# LogicLab1G.net
KiCad netlist of a schematic drawn in EAGLE
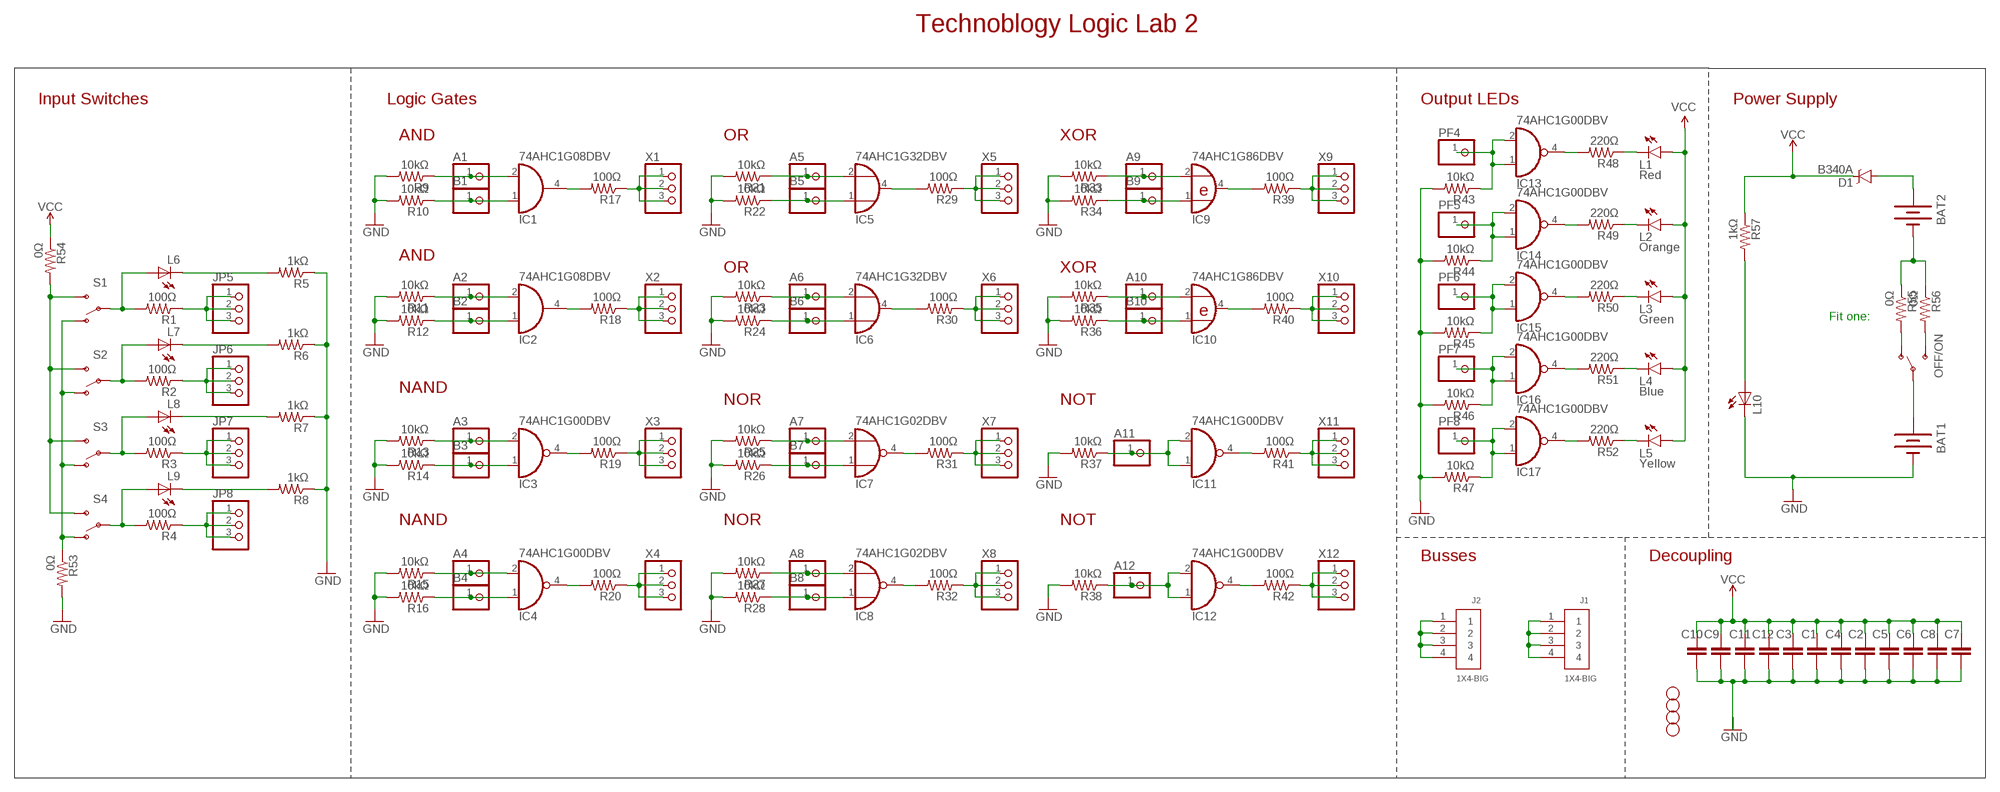
[diagram p0: schematic, sheet 1]

(export (version "E")
  (design (tool "Eeschema 10.0.6"))
  (components
    (comp (ref "A1")
      (value "PINHD-1X1")
      (footprint "eagle-import:1X01")
      (libsource (lib "eagle-import") (part "PINHD-1X1"))
    )
    (comp (ref "A2")
      (value "PINHD-1X1")
      (footprint "eagle-import:1X01")
      (libsource (lib "eagle-import") (part "PINHD-1X1"))
    )
    (comp (ref "A3")
      (value "PINHD-1X1")
      (footprint "eagle-import:1X01")
      (libsource (lib "eagle-import") (part "PINHD-1X1"))
    )
    (comp (ref "A4")
      (value "PINHD-1X1")
      (footprint "eagle-import:1X01")
      (libsource (lib "eagle-import") (part "PINHD-1X1"))
    )
    (comp (ref "A5")
      (value "PINHD-1X1")
      (footprint "eagle-import:1X01")
      (libsource (lib "eagle-import") (part "PINHD-1X1"))
    )
    (comp (ref "A6")
      (value "PINHD-1X1")
      (footprint "eagle-import:1X01")
      (libsource (lib "eagle-import") (part "PINHD-1X1"))
    )
    (comp (ref "A7")
      (value "PINHD-1X1")
      (footprint "eagle-import:1X01")
      (libsource (lib "eagle-import") (part "PINHD-1X1"))
    )
    (comp (ref "A8")
      (value "PINHD-1X1")
      (footprint "eagle-import:1X01")
      (libsource (lib "eagle-import") (part "PINHD-1X1"))
    )
    (comp (ref "A9")
      (value "PINHD-1X1")
      (footprint "eagle-import:1X01")
      (libsource (lib "eagle-import") (part "PINHD-1X1"))
    )
    (comp (ref "A10")
      (value "PINHD-1X1")
      (footprint "eagle-import:1X01")
      (libsource (lib "eagle-import") (part "PINHD-1X1"))
    )
    (comp (ref "A11")
      (value "PINHD-1X1")
      (footprint "eagle-import:1X01")
      (libsource (lib "eagle-import") (part "PINHD-1X1"))
    )
    (comp (ref "A12")
      (value "PINHD-1X1")
      (footprint "eagle-import:1X01")
      (libsource (lib "eagle-import") (part "PINHD-1X1"))
    )
    (comp (ref "B1")
      (value "PINHD-1X1")
      (footprint "eagle-import:1X01")
      (libsource (lib "eagle-import") (part "PINHD-1X1"))
    )
    (comp (ref "B2")
      (value "PINHD-1X1")
      (footprint "eagle-import:1X01")
      (libsource (lib "eagle-import") (part "PINHD-1X1"))
    )
    (comp (ref "B3")
      (value "PINHD-1X1")
      (footprint "eagle-import:1X01")
      (libsource (lib "eagle-import") (part "PINHD-1X1"))
    )
    (comp (ref "B4")
      (value "PINHD-1X1")
      (footprint "eagle-import:1X01")
      (libsource (lib "eagle-import") (part "PINHD-1X1"))
    )
    (comp (ref "B5")
      (value "PINHD-1X1")
      (footprint "eagle-import:1X01")
      (libsource (lib "eagle-import") (part "PINHD-1X1"))
    )
    (comp (ref "B6")
      (value "PINHD-1X1")
      (footprint "eagle-import:1X01")
      (libsource (lib "eagle-import") (part "PINHD-1X1"))
    )
    (comp (ref "B7")
      (value "PINHD-1X1")
      (footprint "eagle-import:1X01")
      (libsource (lib "eagle-import") (part "PINHD-1X1"))
    )
    (comp (ref "B8")
      (value "PINHD-1X1")
      (footprint "eagle-import:1X01")
      (libsource (lib "eagle-import") (part "PINHD-1X1"))
    )
    (comp (ref "B9")
      (value "PINHD-1X1")
      (footprint "eagle-import:1X01")
      (libsource (lib "eagle-import") (part "PINHD-1X1"))
    )
    (comp (ref "B10")
      (value "PINHD-1X1")
      (footprint "eagle-import:1X01")
      (libsource (lib "eagle-import") (part "PINHD-1X1"))
    )
    (comp (ref "BAT1")
      (value "BATTERYAAA-KIT")
      (footprint "eagle-import:BATTERY-AAA-KIT")
      (libsource (lib "eagle-import") (part "BATTERYAAA-KIT"))
    )
    (comp (ref "BAT2")
      (value "BATTERYAAA-KIT")
      (footprint "eagle-import:BATTERY-AAA-KIT")
      (libsource (lib "eagle-import") (part "BATTERYAAA-KIT"))
    )
    (comp (ref "C1")
      (value "100n")
      (footprint "eagle-import:0805")
      (libsource (lib "eagle-import") (part "CAP0805"))
    )
    (comp (ref "C2")
      (value "100n")
      (footprint "eagle-import:0805")
      (libsource (lib "eagle-import") (part "CAP0805"))
    )
    (comp (ref "C3")
      (value "100n")
      (footprint "eagle-import:0805")
      (libsource (lib "eagle-import") (part "CAP0805"))
    )
    (comp (ref "C4")
      (value "10uF")
      (footprint "eagle-import:0805")
      (libsource (lib "eagle-import") (part "CAP0805"))
    )
    (comp (ref "C5")
      (value "100n")
      (footprint "eagle-import:0805")
      (libsource (lib "eagle-import") (part "CAP0805"))
    )
    (comp (ref "C6")
      (value "100n")
      (footprint "eagle-import:0805")
      (libsource (lib "eagle-import") (part "CAP0805"))
    )
    (comp (ref "C7")
      (value "100n")
      (footprint "eagle-import:0805")
      (libsource (lib "eagle-import") (part "CAP0805"))
    )
    (comp (ref "C8")
      (value "100n")
      (footprint "eagle-import:0805")
      (libsource (lib "eagle-import") (part "CAP0805"))
    )
    (comp (ref "C9")
      (value "100n")
      (footprint "eagle-import:0805")
      (libsource (lib "eagle-import") (part "CAP0805"))
    )
    (comp (ref "C10")
      (value "100n")
      (footprint "eagle-import:0805")
      (libsource (lib "eagle-import") (part "CAP0805"))
    )
    (comp (ref "C11")
      (value "10uF")
      (footprint "eagle-import:0805")
      (libsource (lib "eagle-import") (part "CAP0805"))
    )
    (comp (ref "C12")
      (value "100n")
      (footprint "eagle-import:0805")
      (libsource (lib "eagle-import") (part "CAP0805"))
    )
    (comp (ref "D1")
      (value "B340A")
      (footprint "eagle-import:SMA-DIODE")
      (libsource (lib "eagle-import") (part "B340A"))
    )
    (comp (ref "IC1")
      (value "74AHC1G08DBV")
      (footprint "eagle-import:SOT23-5")
      (libsource (lib "eagle-import") (part "741G08DBVAHC"))
    )
    (comp (ref "IC2")
      (value "74AHC1G08DBV")
      (footprint "eagle-import:SOT23-5")
      (libsource (lib "eagle-import") (part "741G08DBVAHC"))
    )
    (comp (ref "IC3")
      (value "74AHC1G00DBV")
      (footprint "eagle-import:SOT23-5")
      (libsource (lib "eagle-import") (part "741G00DBVAHC"))
    )
    (comp (ref "IC4")
      (value "74AHC1G00DBV")
      (footprint "eagle-import:SOT23-5")
      (libsource (lib "eagle-import") (part "741G00DBVAHC"))
    )
    (comp (ref "IC5")
      (value "74AHC1G32DBV")
      (footprint "eagle-import:SOT23-5")
      (libsource (lib "eagle-import") (part "741G32DBVAHC"))
    )
    (comp (ref "IC6")
      (value "74AHC1G32DBV")
      (footprint "eagle-import:SOT23-5")
      (libsource (lib "eagle-import") (part "741G32DBVAHC"))
    )
    (comp (ref "IC7")
      (value "74AHC1G02DBV")
      (footprint "eagle-import:SOT23-5")
      (libsource (lib "eagle-import") (part "741G02DBVAHC"))
    )
    (comp (ref "IC8")
      (value "74AHC1G02DBV")
      (footprint "eagle-import:SOT23-5")
      (libsource (lib "eagle-import") (part "741G02DBVAHC"))
    )
    (comp (ref "IC9")
      (value "74AHC1G86DBV")
      (footprint "eagle-import:SOT23-5")
      (libsource (lib "eagle-import") (part "741G86DBVAHC"))
    )
    (comp (ref "IC10")
      (value "74AHC1G86DBV")
      (footprint "eagle-import:SOT23-5")
      (libsource (lib "eagle-import") (part "741G86DBVAHC"))
    )
    (comp (ref "IC11")
      (value "74AHC1G00DBV")
      (footprint "eagle-import:SOT23-5")
      (libsource (lib "eagle-import") (part "741G00DBVAHC"))
    )
    (comp (ref "IC12")
      (value "74AHC1G00DBV")
      (footprint "eagle-import:SOT23-5")
      (libsource (lib "eagle-import") (part "741G00DBVAHC"))
    )
    (comp (ref "IC13")
      (value "74AHC1G00DBV")
      (footprint "eagle-import:SOT23-5")
      (libsource (lib "eagle-import") (part "741G00DBVAHC"))
    )
    (comp (ref "IC14")
      (value "74AHC1G00DBV")
      (footprint "eagle-import:SOT23-5")
      (libsource (lib "eagle-import") (part "741G00DBVAHC"))
    )
    (comp (ref "IC15")
      (value "74AHC1G00DBV")
      (footprint "eagle-import:SOT23-5")
      (libsource (lib "eagle-import") (part "741G00DBVAHC"))
    )
    (comp (ref "IC16")
      (value "74AHC1G00DBV")
      (footprint "eagle-import:SOT23-5")
      (libsource (lib "eagle-import") (part "741G00DBVAHC"))
    )
    (comp (ref "IC17")
      (value "74AHC1G00DBV")
      (footprint "eagle-import:SOT23-5")
      (libsource (lib "eagle-import") (part "741G00DBVAHC"))
    )
    (comp (ref "J1")
      (value "1X4-BIG")
      (footprint "eagle-import:1X04-BIG")
      (libsource (lib "eagle-import") (part "1X4-BIG"))
    )
    (comp (ref "J2")
      (value "1X4-BIG")
      (footprint "eagle-import:1X04-BIG")
      (libsource (lib "eagle-import") (part "1X4-BIG"))
    )
    (comp (ref "JP1")
      (value "STAND-OFF")
      (footprint "eagle-import:STAND-OFF")
      (libsource (lib "eagle-import") (part "STAND-OFF"))
    )
    (comp (ref "JP2")
      (value "STAND-OFF")
      (footprint "eagle-import:STAND-OFF")
      (libsource (lib "eagle-import") (part "STAND-OFF"))
    )
    (comp (ref "JP3")
      (value "STAND-OFF")
      (footprint "eagle-import:STAND-OFF")
      (libsource (lib "eagle-import") (part "STAND-OFF"))
    )
    (comp (ref "JP4")
      (value "STAND-OFF")
      (footprint "eagle-import:STAND-OFF")
      (libsource (lib "eagle-import") (part "STAND-OFF"))
    )
    (comp (ref "JP5")
      (value "PINHD-1X3")
      (footprint "eagle-import:1X03")
      (libsource (lib "eagle-import") (part "PINHD-1X3"))
    )
    (comp (ref "JP6")
      (value "PINHD-1X3")
      (footprint "eagle-import:1X03")
      (libsource (lib "eagle-import") (part "PINHD-1X3"))
    )
    (comp (ref "JP7")
      (value "PINHD-1X3")
      (footprint "eagle-import:1X03")
      (libsource (lib "eagle-import") (part "PINHD-1X3"))
    )
    (comp (ref "JP8")
      (value "PINHD-1X3")
      (footprint "eagle-import:1X03")
      (libsource (lib "eagle-import") (part "PINHD-1X3"))
    )
    (comp (ref "L1")
      (value "Red")
      (footprint "eagle-import:LED5MM")
      (libsource (lib "eagle-import") (part "LED5MM"))
    )
    (comp (ref "L2")
      (value "Orange")
      (footprint "eagle-import:LED5MM")
      (libsource (lib "eagle-import") (part "LED5MM"))
    )
    (comp (ref "L3")
      (value "Green")
      (footprint "eagle-import:LED5MM")
      (libsource (lib "eagle-import") (part "LED5MM"))
    )
    (comp (ref "L4")
      (value "Blue")
      (footprint "eagle-import:LED5MM")
      (libsource (lib "eagle-import") (part "LED5MM"))
    )
    (comp (ref "L5")
      (value "Yellow")
      (footprint "eagle-import:LED5MM")
      (libsource (lib "eagle-import") (part "LED5MM"))
    )
    (comp (ref "L6")
      (value "LEDCHIPLED_0805")
      (footprint "eagle-import:CHIPLED_0805")
      (libsource (lib "eagle-import") (part "LEDCHIPLED_0805"))
    )
    (comp (ref "L7")
      (value "LEDCHIPLED_0805")
      (footprint "eagle-import:CHIPLED_0805")
      (libsource (lib "eagle-import") (part "LEDCHIPLED_0805"))
    )
    (comp (ref "L8")
      (value "LEDCHIPLED_0805")
      (footprint "eagle-import:CHIPLED_0805")
      (libsource (lib "eagle-import") (part "LEDCHIPLED_0805"))
    )
    (comp (ref "L9")
      (value "LEDCHIPLED_0805")
      (footprint "eagle-import:CHIPLED_0805")
      (libsource (lib "eagle-import") (part "LEDCHIPLED_0805"))
    )
    (comp (ref "L10")
      (value "LEDCHIPLED_0805")
      (footprint "eagle-import:CHIPLED_0805")
      (libsource (lib "eagle-import") (part "LEDCHIPLED_0805"))
    )
    (comp (ref "OFF/ON")
      (value "SWITCH-SPDTKIT")
      (footprint "eagle-import:SWITCH-SPDT_KIT")
      (libsource (lib "eagle-import") (part "SWITCH-SPDTKIT"))
    )
    (comp (ref "PF4")
      (value "PINHD-1X1")
      (footprint "eagle-import:1X01")
      (libsource (lib "eagle-import") (part "PINHD-1X1"))
    )
    (comp (ref "PF5")
      (value "PINHD-1X1")
      (footprint "eagle-import:1X01")
      (libsource (lib "eagle-import") (part "PINHD-1X1"))
    )
    (comp (ref "PF6")
      (value "PINHD-1X1")
      (footprint "eagle-import:1X01")
      (libsource (lib "eagle-import") (part "PINHD-1X1"))
    )
    (comp (ref "PF7")
      (value "PINHD-1X1")
      (footprint "eagle-import:1X01")
      (libsource (lib "eagle-import") (part "PINHD-1X1"))
    )
    (comp (ref "PF8")
      (value "PINHD-1X1")
      (footprint "eagle-import:1X01")
      (libsource (lib "eagle-import") (part "PINHD-1X1"))
    )
    (comp (ref "R1")
      (value "100Ω")
      (footprint "eagle-import:0805")
      (libsource (lib "eagle-import") (part "RESISTOR0805-RES"))
    )
    (comp (ref "R2")
      (value "100Ω")
      (footprint "eagle-import:0805")
      (libsource (lib "eagle-import") (part "RESISTOR0805-RES"))
    )
    (comp (ref "R3")
      (value "100Ω")
      (footprint "eagle-import:0805")
      (libsource (lib "eagle-import") (part "RESISTOR0805-RES"))
    )
    (comp (ref "R4")
      (value "100Ω")
      (footprint "eagle-import:0805")
      (libsource (lib "eagle-import") (part "RESISTOR0805-RES"))
    )
    (comp (ref "R5")
      (value "1kΩ")
      (footprint "eagle-import:0805")
      (libsource (lib "eagle-import") (part "RESISTOR0805-RES"))
    )
    (comp (ref "R6")
      (value "1kΩ")
      (footprint "eagle-import:0805")
      (libsource (lib "eagle-import") (part "RESISTOR0805-RES"))
    )
    (comp (ref "R7")
      (value "1kΩ")
      (footprint "eagle-import:0805")
      (libsource (lib "eagle-import") (part "RESISTOR0805-RES"))
    )
    (comp (ref "R8")
      (value "1kΩ")
      (footprint "eagle-import:0805")
      (libsource (lib "eagle-import") (part "RESISTOR0805-RES"))
    )
    (comp (ref "R9")
      (value "10kΩ")
      (footprint "eagle-import:0805")
      (libsource (lib "eagle-import") (part "RESISTOR0805-RES"))
    )
    (comp (ref "R10")
      (value "10kΩ")
      (footprint "eagle-import:0805")
      (libsource (lib "eagle-import") (part "RESISTOR0805-RES"))
    )
    (comp (ref "R11")
      (value "10kΩ")
      (footprint "eagle-import:0805")
      (libsource (lib "eagle-import") (part "RESISTOR0805-RES"))
    )
    (comp (ref "R12")
      (value "10kΩ")
      (footprint "eagle-import:0805")
      (libsource (lib "eagle-import") (part "RESISTOR0805-RES"))
    )
    (comp (ref "R13")
      (value "10kΩ")
      (footprint "eagle-import:0805")
      (libsource (lib "eagle-import") (part "RESISTOR0805-RES"))
    )
    (comp (ref "R14")
      (value "10kΩ")
      (footprint "eagle-import:0805")
      (libsource (lib "eagle-import") (part "RESISTOR0805-RES"))
    )
    (comp (ref "R15")
      (value "10kΩ")
      (footprint "eagle-import:0805")
      (libsource (lib "eagle-import") (part "RESISTOR0805-RES"))
    )
    (comp (ref "R16")
      (value "10kΩ")
      (footprint "eagle-import:0805")
      (libsource (lib "eagle-import") (part "RESISTOR0805-RES"))
    )
    (comp (ref "R17")
      (value "100Ω")
      (footprint "eagle-import:0805")
      (libsource (lib "eagle-import") (part "RESISTOR0805-RES"))
    )
    (comp (ref "R18")
      (value "100Ω")
      (footprint "eagle-import:0805")
      (libsource (lib "eagle-import") (part "RESISTOR0805-RES"))
    )
    (comp (ref "R19")
      (value "100Ω")
      (footprint "eagle-import:0805")
      (libsource (lib "eagle-import") (part "RESISTOR0805-RES"))
    )
    (comp (ref "R20")
      (value "100Ω")
      (footprint "eagle-import:0805")
      (libsource (lib "eagle-import") (part "RESISTOR0805-RES"))
    )
    (comp (ref "R21")
      (value "10kΩ")
      (footprint "eagle-import:0805")
      (libsource (lib "eagle-import") (part "RESISTOR0805-RES"))
    )
    (comp (ref "R22")
      (value "10kΩ")
      (footprint "eagle-import:0805")
      (libsource (lib "eagle-import") (part "RESISTOR0805-RES"))
    )
    (comp (ref "R23")
      (value "10kΩ")
      (footprint "eagle-import:0805")
      (libsource (lib "eagle-import") (part "RESISTOR0805-RES"))
    )
    (comp (ref "R24")
      (value "10kΩ")
      (footprint "eagle-import:0805")
      (libsource (lib "eagle-import") (part "RESISTOR0805-RES"))
    )
    (comp (ref "R25")
      (value "10kΩ")
      (footprint "eagle-import:0805")
      (libsource (lib "eagle-import") (part "RESISTOR0805-RES"))
    )
    (comp (ref "R26")
      (value "10kΩ")
      (footprint "eagle-import:0805")
      (libsource (lib "eagle-import") (part "RESISTOR0805-RES"))
    )
    (comp (ref "R27")
      (value "10kΩ")
      (footprint "eagle-import:0805")
      (libsource (lib "eagle-import") (part "RESISTOR0805-RES"))
    )
    (comp (ref "R28")
      (value "10kΩ")
      (footprint "eagle-import:0805")
      (libsource (lib "eagle-import") (part "RESISTOR0805-RES"))
    )
    (comp (ref "R29")
      (value "100Ω")
      (footprint "eagle-import:0805")
      (libsource (lib "eagle-import") (part "RESISTOR0805-RES"))
    )
    (comp (ref "R30")
      (value "100Ω")
      (footprint "eagle-import:0805")
      (libsource (lib "eagle-import") (part "RESISTOR0805-RES"))
    )
    (comp (ref "R31")
      (value "100Ω")
      (footprint "eagle-import:0805")
      (libsource (lib "eagle-import") (part "RESISTOR0805-RES"))
    )
    (comp (ref "R32")
      (value "100Ω")
      (footprint "eagle-import:0805")
      (libsource (lib "eagle-import") (part "RESISTOR0805-RES"))
    )
    (comp (ref "R33")
      (value "10kΩ")
      (footprint "eagle-import:0805")
      (libsource (lib "eagle-import") (part "RESISTOR0805-RES"))
    )
    (comp (ref "R34")
      (value "10kΩ")
      (footprint "eagle-import:0805")
      (libsource (lib "eagle-import") (part "RESISTOR0805-RES"))
    )
    (comp (ref "R35")
      (value "10kΩ")
      (footprint "eagle-import:0805")
      (libsource (lib "eagle-import") (part "RESISTOR0805-RES"))
    )
    (comp (ref "R36")
      (value "10kΩ")
      (footprint "eagle-import:0805")
      (libsource (lib "eagle-import") (part "RESISTOR0805-RES"))
    )
    (comp (ref "R37")
      (value "10kΩ")
      (footprint "eagle-import:0805")
      (libsource (lib "eagle-import") (part "RESISTOR0805-RES"))
    )
    (comp (ref "R38")
      (value "10kΩ")
      (footprint "eagle-import:0805")
      (libsource (lib "eagle-import") (part "RESISTOR0805-RES"))
    )
    (comp (ref "R39")
      (value "100Ω")
      (footprint "eagle-import:0805")
      (libsource (lib "eagle-import") (part "RESISTOR0805-RES"))
    )
    (comp (ref "R40")
      (value "100Ω")
      (footprint "eagle-import:0805")
      (libsource (lib "eagle-import") (part "RESISTOR0805-RES"))
    )
    (comp (ref "R41")
      (value "100Ω")
      (footprint "eagle-import:0805")
      (libsource (lib "eagle-import") (part "RESISTOR0805-RES"))
    )
    (comp (ref "R42")
      (value "100Ω")
      (footprint "eagle-import:0805")
      (libsource (lib "eagle-import") (part "RESISTOR0805-RES"))
    )
    (comp (ref "R43")
      (value "10kΩ")
      (footprint "eagle-import:0805")
      (libsource (lib "eagle-import") (part "RESISTOR0805-RES"))
    )
    (comp (ref "R44")
      (value "10kΩ")
      (footprint "eagle-import:0805")
      (libsource (lib "eagle-import") (part "RESISTOR0805-RES"))
    )
    (comp (ref "R45")
      (value "10kΩ")
      (footprint "eagle-import:0805")
      (libsource (lib "eagle-import") (part "RESISTOR0805-RES"))
    )
    (comp (ref "R46")
      (value "10kΩ")
      (footprint "eagle-import:0805")
      (libsource (lib "eagle-import") (part "RESISTOR0805-RES"))
    )
    (comp (ref "R47")
      (value "10kΩ")
      (footprint "eagle-import:0805")
      (libsource (lib "eagle-import") (part "RESISTOR0805-RES"))
    )
    (comp (ref "R48")
      (value "220Ω")
      (footprint "eagle-import:0805")
      (libsource (lib "eagle-import") (part "RESISTOR0805-RES"))
    )
    (comp (ref "R49")
      (value "220Ω")
      (footprint "eagle-import:0805")
      (libsource (lib "eagle-import") (part "RESISTOR0805-RES"))
    )
    (comp (ref "R50")
      (value "220Ω")
      (footprint "eagle-import:0805")
      (libsource (lib "eagle-import") (part "RESISTOR0805-RES"))
    )
    (comp (ref "R51")
      (value "220Ω")
      (footprint "eagle-import:0805")
      (libsource (lib "eagle-import") (part "RESISTOR0805-RES"))
    )
    (comp (ref "R52")
      (value "220Ω")
      (footprint "eagle-import:0805")
      (libsource (lib "eagle-import") (part "RESISTOR0805-RES"))
    )
    (comp (ref "R53")
      (value "0Ω")
      (footprint "eagle-import:0805")
      (libsource (lib "eagle-import") (part "RESISTOR0805-RES"))
    )
    (comp (ref "R54")
      (value "0Ω")
      (footprint "eagle-import:0805")
      (libsource (lib "eagle-import") (part "RESISTOR0805-RES"))
    )
    (comp (ref "R55")
      (value "0Ω")
      (footprint "eagle-import:0805")
      (libsource (lib "eagle-import") (part "RESISTOR0805-RES"))
    )
    (comp (ref "R56")
      (value "0Ω")
      (footprint "eagle-import:0805")
      (libsource (lib "eagle-import") (part "RESISTOR0805-RES"))
    )
    (comp (ref "R57")
      (value "1kΩ")
      (footprint "eagle-import:0805")
      (libsource (lib "eagle-import") (part "RESISTOR0805-RES"))
    )
    (comp (ref "S1")
      (value "SWITCH-SPDTKIT")
      (footprint "eagle-import:SWITCH-SPDT_KIT")
      (libsource (lib "eagle-import") (part "SWITCH-SPDTKIT"))
    )
    (comp (ref "S2")
      (value "SWITCH-SPDTKIT")
      (footprint "eagle-import:SWITCH-SPDT_KIT")
      (libsource (lib "eagle-import") (part "SWITCH-SPDTKIT"))
    )
    (comp (ref "S3")
      (value "SWITCH-SPDTKIT")
      (footprint "eagle-import:SWITCH-SPDT_KIT")
      (libsource (lib "eagle-import") (part "SWITCH-SPDTKIT"))
    )
    (comp (ref "S4")
      (value "SWITCH-SPDTKIT")
      (footprint "eagle-import:SWITCH-SPDT_KIT")
      (libsource (lib "eagle-import") (part "SWITCH-SPDTKIT"))
    )
    (comp (ref "X1")
      (value "PINHD-1X3")
      (footprint "eagle-import:1X03")
      (libsource (lib "eagle-import") (part "PINHD-1X3"))
    )
    (comp (ref "X2")
      (value "PINHD-1X3")
      (footprint "eagle-import:1X03")
      (libsource (lib "eagle-import") (part "PINHD-1X3"))
    )
    (comp (ref "X3")
      (value "PINHD-1X3")
      (footprint "eagle-import:1X03")
      (libsource (lib "eagle-import") (part "PINHD-1X3"))
    )
    (comp (ref "X4")
      (value "PINHD-1X3")
      (footprint "eagle-import:1X03")
      (libsource (lib "eagle-import") (part "PINHD-1X3"))
    )
    (comp (ref "X5")
      (value "PINHD-1X3")
      (footprint "eagle-import:1X03")
      (libsource (lib "eagle-import") (part "PINHD-1X3"))
    )
    (comp (ref "X6")
      (value "PINHD-1X3")
      (footprint "eagle-import:1X03")
      (libsource (lib "eagle-import") (part "PINHD-1X3"))
    )
    (comp (ref "X7")
      (value "PINHD-1X3")
      (footprint "eagle-import:1X03")
      (libsource (lib "eagle-import") (part "PINHD-1X3"))
    )
    (comp (ref "X8")
      (value "PINHD-1X3")
      (footprint "eagle-import:1X03")
      (libsource (lib "eagle-import") (part "PINHD-1X3"))
    )
    (comp (ref "X9")
      (value "PINHD-1X3")
      (footprint "eagle-import:1X03")
      (libsource (lib "eagle-import") (part "PINHD-1X3"))
    )
    (comp (ref "X10")
      (value "PINHD-1X3")
      (footprint "eagle-import:1X03")
      (libsource (lib "eagle-import") (part "PINHD-1X3"))
    )
    (comp (ref "X11")
      (value "PINHD-1X3")
      (footprint "eagle-import:1X03")
      (libsource (lib "eagle-import") (part "PINHD-1X3"))
    )
    (comp (ref "X12")
      (value "PINHD-1X3")
      (footprint "eagle-import:1X03")
      (libsource (lib "eagle-import") (part "PINHD-1X3"))
    )
  )
  (nets
    (net (code "1") (name "GND") (class "Default")
      (node (ref "BAT1") (pin "GND@1") (pinfunction "-_GND@1") (pintype "power_in"))
      (node (ref "C1") (pin "2") (pinfunction "2_2") (pintype "passive"))
      (node (ref "C10") (pin "2") (pinfunction "2_2") (pintype "passive"))
      (node (ref "C11") (pin "2") (pinfunction "2_2") (pintype "passive"))
      (node (ref "C12") (pin "2") (pinfunction "2_2") (pintype "passive"))
      (node (ref "C2") (pin "2") (pinfunction "2_2") (pintype "passive"))
      (node (ref "C3") (pin "2") (pinfunction "2_2") (pintype "passive"))
      (node (ref "C4") (pin "2") (pinfunction "2_2") (pintype "passive"))
      (node (ref "C5") (pin "2") (pinfunction "2_2") (pintype "passive"))
      (node (ref "C6") (pin "2") (pinfunction "2_2") (pintype "passive"))
      (node (ref "C7") (pin "2") (pinfunction "2_2") (pintype "passive"))
      (node (ref "C8") (pin "2") (pinfunction "2_2") (pintype "passive"))
      (node (ref "C9") (pin "2") (pinfunction "2_2") (pintype "passive"))
      (node (ref "L10") (pin "C") (pinfunction "C_C") (pintype "passive"))
      (node (ref "R10") (pin "2") (pinfunction "2_2") (pintype "passive"))
      (node (ref "R11") (pin "2") (pinfunction "2_2") (pintype "passive"))
      (node (ref "R12") (pin "2") (pinfunction "2_2") (pintype "passive"))
      (node (ref "R13") (pin "2") (pinfunction "2_2") (pintype "passive"))
      (node (ref "R14") (pin "2") (pinfunction "2_2") (pintype "passive"))
      (node (ref "R15") (pin "2") (pinfunction "2_2") (pintype "passive"))
      (node (ref "R16") (pin "2") (pinfunction "2_2") (pintype "passive"))
      (node (ref "R21") (pin "2") (pinfunction "2_2") (pintype "passive"))
      (node (ref "R22") (pin "2") (pinfunction "2_2") (pintype "passive"))
      (node (ref "R23") (pin "2") (pinfunction "2_2") (pintype "passive"))
      (node (ref "R24") (pin "2") (pinfunction "2_2") (pintype "passive"))
      (node (ref "R25") (pin "2") (pinfunction "2_2") (pintype "passive"))
      (node (ref "R26") (pin "2") (pinfunction "2_2") (pintype "passive"))
      (node (ref "R27") (pin "2") (pinfunction "2_2") (pintype "passive"))
      (node (ref "R28") (pin "2") (pinfunction "2_2") (pintype "passive"))
      (node (ref "R33") (pin "2") (pinfunction "2_2") (pintype "passive"))
      (node (ref "R34") (pin "2") (pinfunction "2_2") (pintype "passive"))
      (node (ref "R35") (pin "2") (pinfunction "2_2") (pintype "passive"))
      (node (ref "R36") (pin "2") (pinfunction "2_2") (pintype "passive"))
      (node (ref "R37") (pin "2") (pinfunction "2_2") (pintype "passive"))
      (node (ref "R38") (pin "2") (pinfunction "2_2") (pintype "passive"))
      (node (ref "R43") (pin "2") (pinfunction "2_2") (pintype "passive"))
      (node (ref "R44") (pin "2") (pinfunction "2_2") (pintype "passive"))
      (node (ref "R45") (pin "2") (pinfunction "2_2") (pintype "passive"))
      (node (ref "R46") (pin "2") (pinfunction "2_2") (pintype "passive"))
      (node (ref "R47") (pin "2") (pinfunction "2_2") (pintype "passive"))
      (node (ref "R5") (pin "1") (pinfunction "1_1") (pintype "passive"))
      (node (ref "R53") (pin "2") (pinfunction "2_2") (pintype "passive"))
      (node (ref "R6") (pin "1") (pinfunction "1_1") (pintype "passive"))
      (node (ref "R7") (pin "1") (pinfunction "1_1") (pintype "passive"))
      (node (ref "R8") (pin "1") (pinfunction "1_1") (pintype "passive"))
      (node (ref "R9") (pin "2") (pinfunction "2_2") (pintype "passive"))
    )
    (net (code "2") (name "Net-(BAT1-+)") (class "Default")
      (node (ref "BAT1") (pin "PWR@1") (pinfunction "+_PWR@1") (pintype "power_in"))
      (node (ref "OFF/ON") (pin "2") (pinfunction "P_2") (pintype "passive"))
    )
    (net (code "3") (name "Net-(BAT2-+)") (class "Default")
      (node (ref "BAT2") (pin "PWR@1") (pinfunction "+_PWR@1") (pintype "power_in"))
      (node (ref "D1") (pin "A") (pinfunction "A_A") (pintype "passive"))
    )
    (net (code "4") (name "Net-(BAT2--)") (class "Default")
      (node (ref "BAT2") (pin "GND@1") (pinfunction "-_GND@1") (pintype "power_in"))
      (node (ref "R55") (pin "1") (pinfunction "1_1") (pintype "passive"))
      (node (ref "R56") (pin "1") (pinfunction "1_1") (pintype "passive"))
    )
    (net (code "5") (name "Net-(IC1A-I0)") (class "Default")
      (node (ref "B1") (pin "1") (pinfunction "1_1") (pintype "passive"))
      (node (ref "IC1") (pin "1") (pinfunction "I0_1") (pintype "input"))
      (node (ref "R10") (pin "1") (pinfunction "1_1") (pintype "passive"))
    )
    (net (code "6") (name "Net-(IC1A-I1)") (class "Default")
      (node (ref "A1") (pin "1") (pinfunction "1_1") (pintype "passive"))
      (node (ref "IC1") (pin "2") (pinfunction "I1_2") (pintype "input"))
      (node (ref "R9") (pin "1") (pinfunction "1_1") (pintype "passive"))
    )
    (net (code "7") (name "Net-(IC1A-O)") (class "Default")
      (node (ref "IC1") (pin "4") (pinfunction "O_4") (pintype "output"))
      (node (ref "R17") (pin "2") (pinfunction "2_2") (pintype "passive"))
    )
    (net (code "8") (name "Net-(IC2A-I0)") (class "Default")
      (node (ref "B2") (pin "1") (pinfunction "1_1") (pintype "passive"))
      (node (ref "IC2") (pin "1") (pinfunction "I0_1") (pintype "input"))
      (node (ref "R12") (pin "1") (pinfunction "1_1") (pintype "passive"))
    )
    (net (code "9") (name "Net-(IC2A-I1)") (class "Default")
      (node (ref "A2") (pin "1") (pinfunction "1_1") (pintype "passive"))
      (node (ref "IC2") (pin "2") (pinfunction "I1_2") (pintype "input"))
      (node (ref "R11") (pin "1") (pinfunction "1_1") (pintype "passive"))
    )
    (net (code "10") (name "Net-(IC2A-O)") (class "Default")
      (node (ref "IC2") (pin "4") (pinfunction "O_4") (pintype "output"))
      (node (ref "R18") (pin "2") (pinfunction "2_2") (pintype "passive"))
    )
    (net (code "11") (name "Net-(IC3A-I0)") (class "Default")
      (node (ref "B3") (pin "1") (pinfunction "1_1") (pintype "passive"))
      (node (ref "IC3") (pin "1") (pinfunction "I0_1") (pintype "input"))
      (node (ref "R14") (pin "1") (pinfunction "1_1") (pintype "passive"))
    )
    (net (code "12") (name "Net-(IC3A-I1)") (class "Default")
      (node (ref "A3") (pin "1") (pinfunction "1_1") (pintype "passive"))
      (node (ref "IC3") (pin "2") (pinfunction "I1_2") (pintype "input"))
      (node (ref "R13") (pin "1") (pinfunction "1_1") (pintype "passive"))
    )
    (net (code "13") (name "Net-(IC3A-O)") (class "Default")
      (node (ref "IC3") (pin "4") (pinfunction "O_4") (pintype "output"))
      (node (ref "R19") (pin "2") (pinfunction "2_2") (pintype "passive"))
    )
    (net (code "14") (name "Net-(IC4A-I0)") (class "Default")
      (node (ref "B4") (pin "1") (pinfunction "1_1") (pintype "passive"))
      (node (ref "IC4") (pin "1") (pinfunction "I0_1") (pintype "input"))
      (node (ref "R16") (pin "1") (pinfunction "1_1") (pintype "passive"))
    )
    (net (code "15") (name "Net-(IC4A-I1)") (class "Default")
      (node (ref "A4") (pin "1") (pinfunction "1_1") (pintype "passive"))
      (node (ref "IC4") (pin "2") (pinfunction "I1_2") (pintype "input"))
      (node (ref "R15") (pin "1") (pinfunction "1_1") (pintype "passive"))
    )
    (net (code "16") (name "Net-(IC4A-O)") (class "Default")
      (node (ref "IC4") (pin "4") (pinfunction "O_4") (pintype "output"))
      (node (ref "R20") (pin "2") (pinfunction "2_2") (pintype "passive"))
    )
    (net (code "17") (name "Net-(IC5A-I0)") (class "Default")
      (node (ref "B5") (pin "1") (pinfunction "1_1") (pintype "passive"))
      (node (ref "IC5") (pin "1") (pinfunction "I0_1") (pintype "input"))
      (node (ref "R22") (pin "1") (pinfunction "1_1") (pintype "passive"))
    )
    (net (code "18") (name "Net-(IC5A-I1)") (class "Default")
      (node (ref "A5") (pin "1") (pinfunction "1_1") (pintype "passive"))
      (node (ref "IC5") (pin "2") (pinfunction "I1_2") (pintype "input"))
      (node (ref "R21") (pin "1") (pinfunction "1_1") (pintype "passive"))
    )
    (net (code "19") (name "Net-(IC5A-O)") (class "Default")
      (node (ref "IC5") (pin "4") (pinfunction "O_4") (pintype "output"))
      (node (ref "R29") (pin "2") (pinfunction "2_2") (pintype "passive"))
    )
    (net (code "20") (name "Net-(IC6A-I0)") (class "Default")
      (node (ref "B6") (pin "1") (pinfunction "1_1") (pintype "passive"))
      (node (ref "IC6") (pin "1") (pinfunction "I0_1") (pintype "input"))
      (node (ref "R24") (pin "1") (pinfunction "1_1") (pintype "passive"))
    )
    (net (code "21") (name "Net-(IC6A-I1)") (class "Default")
      (node (ref "A6") (pin "1") (pinfunction "1_1") (pintype "passive"))
      (node (ref "IC6") (pin "2") (pinfunction "I1_2") (pintype "input"))
      (node (ref "R23") (pin "1") (pinfunction "1_1") (pintype "passive"))
    )
    (net (code "22") (name "Net-(IC6A-O)") (class "Default")
      (node (ref "IC6") (pin "4") (pinfunction "O_4") (pintype "output"))
      (node (ref "R30") (pin "2") (pinfunction "2_2") (pintype "passive"))
    )
    (net (code "23") (name "Net-(IC7A-I0)") (class "Default")
      (node (ref "B7") (pin "1") (pinfunction "1_1") (pintype "passive"))
      (node (ref "IC7") (pin "1") (pinfunction "I0_1") (pintype "input"))
      (node (ref "R26") (pin "1") (pinfunction "1_1") (pintype "passive"))
    )
    (net (code "24") (name "Net-(IC7A-I1)") (class "Default")
      (node (ref "A7") (pin "1") (pinfunction "1_1") (pintype "passive"))
      (node (ref "IC7") (pin "2") (pinfunction "I1_2") (pintype "input"))
      (node (ref "R25") (pin "1") (pinfunction "1_1") (pintype "passive"))
    )
    (net (code "25") (name "Net-(IC7A-O)") (class "Default")
      (node (ref "IC7") (pin "4") (pinfunction "O_4") (pintype "output"))
      (node (ref "R31") (pin "2") (pinfunction "2_2") (pintype "passive"))
    )
    (net (code "26") (name "Net-(IC8A-I0)") (class "Default")
      (node (ref "B8") (pin "1") (pinfunction "1_1") (pintype "passive"))
      (node (ref "IC8") (pin "1") (pinfunction "I0_1") (pintype "input"))
      (node (ref "R28") (pin "1") (pinfunction "1_1") (pintype "passive"))
    )
    (net (code "27") (name "Net-(IC8A-I1)") (class "Default")
      (node (ref "A8") (pin "1") (pinfunction "1_1") (pintype "passive"))
      (node (ref "IC8") (pin "2") (pinfunction "I1_2") (pintype "input"))
      (node (ref "R27") (pin "1") (pinfunction "1_1") (pintype "passive"))
    )
    (net (code "28") (name "Net-(IC8A-O)") (class "Default")
      (node (ref "IC8") (pin "4") (pinfunction "O_4") (pintype "output"))
      (node (ref "R32") (pin "2") (pinfunction "2_2") (pintype "passive"))
    )
    (net (code "29") (name "Net-(IC9A-I0)") (class "Default")
      (node (ref "B9") (pin "1") (pinfunction "1_1") (pintype "passive"))
      (node (ref "IC9") (pin "1") (pinfunction "I0_1") (pintype "input"))
      (node (ref "R34") (pin "1") (pinfunction "1_1") (pintype "passive"))
    )
    (net (code "30") (name "Net-(IC9A-I1)") (class "Default")
      (node (ref "A9") (pin "1") (pinfunction "1_1") (pintype "passive"))
      (node (ref "IC9") (pin "2") (pinfunction "I1_2") (pintype "input"))
      (node (ref "R33") (pin "1") (pinfunction "1_1") (pintype "passive"))
    )
    (net (code "31") (name "Net-(IC9A-O)") (class "Default")
      (node (ref "IC9") (pin "4") (pinfunction "O_4") (pintype "output"))
      (node (ref "R39") (pin "2") (pinfunction "2_2") (pintype "passive"))
    )
    (net (code "32") (name "Net-(IC10A-I0)") (class "Default")
      (node (ref "B10") (pin "1") (pinfunction "1_1") (pintype "passive"))
      (node (ref "IC10") (pin "1") (pinfunction "I0_1") (pintype "input"))
      (node (ref "R36") (pin "1") (pinfunction "1_1") (pintype "passive"))
    )
    (net (code "33") (name "Net-(IC10A-I1)") (class "Default")
      (node (ref "A10") (pin "1") (pinfunction "1_1") (pintype "passive"))
      (node (ref "IC10") (pin "2") (pinfunction "I1_2") (pintype "input"))
      (node (ref "R35") (pin "1") (pinfunction "1_1") (pintype "passive"))
    )
    (net (code "34") (name "Net-(IC10A-O)") (class "Default")
      (node (ref "IC10") (pin "4") (pinfunction "O_4") (pintype "output"))
      (node (ref "R40") (pin "2") (pinfunction "2_2") (pintype "passive"))
    )
    (net (code "35") (name "Net-(IC11A-I0)") (class "Default")
      (node (ref "A11") (pin "1") (pinfunction "1_1") (pintype "passive"))
      (node (ref "IC11") (pin "1") (pinfunction "I0_1") (pintype "input"))
      (node (ref "IC11") (pin "2") (pinfunction "I1_2") (pintype "input"))
      (node (ref "R37") (pin "1") (pinfunction "1_1") (pintype "passive"))
    )
    (net (code "36") (name "Net-(IC11A-O)") (class "Default")
      (node (ref "IC11") (pin "4") (pinfunction "O_4") (pintype "output"))
      (node (ref "R41") (pin "2") (pinfunction "2_2") (pintype "passive"))
    )
    (net (code "37") (name "Net-(IC12A-I0)") (class "Default")
      (node (ref "A12") (pin "1") (pinfunction "1_1") (pintype "passive"))
      (node (ref "IC12") (pin "1") (pinfunction "I0_1") (pintype "input"))
      (node (ref "IC12") (pin "2") (pinfunction "I1_2") (pintype "input"))
      (node (ref "R38") (pin "1") (pinfunction "1_1") (pintype "passive"))
    )
    (net (code "38") (name "Net-(IC12A-O)") (class "Default")
      (node (ref "IC12") (pin "4") (pinfunction "O_4") (pintype "output"))
      (node (ref "R42") (pin "2") (pinfunction "2_2") (pintype "passive"))
    )
    (net (code "39") (name "Net-(IC13A-I0)") (class "Default")
      (node (ref "IC13") (pin "1") (pinfunction "I0_1") (pintype "input"))
      (node (ref "IC13") (pin "2") (pinfunction "I1_2") (pintype "input"))
      (node (ref "PF4") (pin "1") (pinfunction "1_1") (pintype "passive"))
      (node (ref "R43") (pin "1") (pinfunction "1_1") (pintype "passive"))
    )
    (net (code "40") (name "Net-(IC13A-O)") (class "Default")
      (node (ref "IC13") (pin "4") (pinfunction "O_4") (pintype "output"))
      (node (ref "R48") (pin "2") (pinfunction "2_2") (pintype "passive"))
    )
    (net (code "41") (name "Net-(IC14A-I0)") (class "Default")
      (node (ref "IC14") (pin "1") (pinfunction "I0_1") (pintype "input"))
      (node (ref "IC14") (pin "2") (pinfunction "I1_2") (pintype "input"))
      (node (ref "PF5") (pin "1") (pinfunction "1_1") (pintype "passive"))
      (node (ref "R44") (pin "1") (pinfunction "1_1") (pintype "passive"))
    )
    (net (code "42") (name "Net-(IC14A-O)") (class "Default")
      (node (ref "IC14") (pin "4") (pinfunction "O_4") (pintype "output"))
      (node (ref "R49") (pin "2") (pinfunction "2_2") (pintype "passive"))
    )
    (net (code "43") (name "Net-(IC15A-I0)") (class "Default")
      (node (ref "IC15") (pin "1") (pinfunction "I0_1") (pintype "input"))
      (node (ref "IC15") (pin "2") (pinfunction "I1_2") (pintype "input"))
      (node (ref "PF6") (pin "1") (pinfunction "1_1") (pintype "passive"))
      (node (ref "R45") (pin "1") (pinfunction "1_1") (pintype "passive"))
    )
    (net (code "44") (name "Net-(IC15A-O)") (class "Default")
      (node (ref "IC15") (pin "4") (pinfunction "O_4") (pintype "output"))
      (node (ref "R50") (pin "2") (pinfunction "2_2") (pintype "passive"))
    )
    (net (code "45") (name "Net-(IC16A-I0)") (class "Default")
      (node (ref "IC16") (pin "1") (pinfunction "I0_1") (pintype "input"))
      (node (ref "IC16") (pin "2") (pinfunction "I1_2") (pintype "input"))
      (node (ref "PF7") (pin "1") (pinfunction "1_1") (pintype "passive"))
      (node (ref "R46") (pin "1") (pinfunction "1_1") (pintype "passive"))
    )
    (net (code "46") (name "Net-(IC16A-O)") (class "Default")
      (node (ref "IC16") (pin "4") (pinfunction "O_4") (pintype "output"))
      (node (ref "R51") (pin "2") (pinfunction "2_2") (pintype "passive"))
    )
    (net (code "47") (name "Net-(IC17A-I0)") (class "Default")
      (node (ref "IC17") (pin "1") (pinfunction "I0_1") (pintype "input"))
      (node (ref "IC17") (pin "2") (pinfunction "I1_2") (pintype "input"))
      (node (ref "PF8") (pin "1") (pinfunction "1_1") (pintype "passive"))
      (node (ref "R47") (pin "1") (pinfunction "1_1") (pintype "passive"))
    )
    (net (code "48") (name "Net-(IC17A-O)") (class "Default")
      (node (ref "IC17") (pin "4") (pinfunction "O_4") (pintype "output"))
      (node (ref "R52") (pin "2") (pinfunction "2_2") (pintype "passive"))
    )
    (net (code "49") (name "Net-(J1-Pad1)") (class "Default")
      (node (ref "J1") (pin "1") (pinfunction "1_1") (pintype "bidirectional"))
      (node (ref "J1") (pin "2") (pinfunction "2_2") (pintype "bidirectional"))
      (node (ref "J1") (pin "3") (pinfunction "3_3") (pintype "bidirectional"))
      (node (ref "J1") (pin "4") (pinfunction "4_4") (pintype "bidirectional"))
    )
    (net (code "50") (name "Net-(J2-Pad1)") (class "Default")
      (node (ref "J2") (pin "1") (pinfunction "1_1") (pintype "bidirectional"))
      (node (ref "J2") (pin "2") (pinfunction "2_2") (pintype "bidirectional"))
      (node (ref "J2") (pin "3") (pinfunction "3_3") (pintype "bidirectional"))
      (node (ref "J2") (pin "4") (pinfunction "4_4") (pintype "bidirectional"))
    )
    (net (code "51") (name "Net-(JP5-Pad1)") (class "Default")
      (node (ref "JP5") (pin "1") (pinfunction "1_1") (pintype "passive"))
      (node (ref "JP5") (pin "2") (pinfunction "2_2") (pintype "passive"))
      (node (ref "JP5") (pin "3") (pinfunction "3_3") (pintype "passive"))
      (node (ref "R1") (pin "1") (pinfunction "1_1") (pintype "passive"))
    )
    (net (code "52") (name "Net-(JP6-Pad1)") (class "Default")
      (node (ref "JP6") (pin "1") (pinfunction "1_1") (pintype "passive"))
      (node (ref "JP6") (pin "2") (pinfunction "2_2") (pintype "passive"))
      (node (ref "JP6") (pin "3") (pinfunction "3_3") (pintype "passive"))
      (node (ref "R2") (pin "1") (pinfunction "1_1") (pintype "passive"))
    )
    (net (code "53") (name "Net-(JP7-Pad1)") (class "Default")
      (node (ref "JP7") (pin "1") (pinfunction "1_1") (pintype "passive"))
      (node (ref "JP7") (pin "2") (pinfunction "2_2") (pintype "passive"))
      (node (ref "JP7") (pin "3") (pinfunction "3_3") (pintype "passive"))
      (node (ref "R3") (pin "1") (pinfunction "1_1") (pintype "passive"))
    )
    (net (code "54") (name "Net-(JP8-Pad1)") (class "Default")
      (node (ref "JP8") (pin "1") (pinfunction "1_1") (pintype "passive"))
      (node (ref "JP8") (pin "2") (pinfunction "2_2") (pintype "passive"))
      (node (ref "JP8") (pin "3") (pinfunction "3_3") (pintype "passive"))
      (node (ref "R4") (pin "1") (pinfunction "1_1") (pintype "passive"))
    )
    (net (code "55") (name "Net-(L1-C)") (class "Default")
      (node (ref "L1") (pin "K") (pinfunction "C_K") (pintype "passive"))
      (node (ref "R48") (pin "1") (pinfunction "1_1") (pintype "passive"))
    )
    (net (code "56") (name "Net-(L2-C)") (class "Default")
      (node (ref "L2") (pin "K") (pinfunction "C_K") (pintype "passive"))
      (node (ref "R49") (pin "1") (pinfunction "1_1") (pintype "passive"))
    )
    (net (code "57") (name "Net-(L3-C)") (class "Default")
      (node (ref "L3") (pin "K") (pinfunction "C_K") (pintype "passive"))
      (node (ref "R50") (pin "1") (pinfunction "1_1") (pintype "passive"))
    )
    (net (code "58") (name "Net-(L4-C)") (class "Default")
      (node (ref "L4") (pin "K") (pinfunction "C_K") (pintype "passive"))
      (node (ref "R51") (pin "1") (pinfunction "1_1") (pintype "passive"))
    )
    (net (code "59") (name "Net-(L5-C)") (class "Default")
      (node (ref "L5") (pin "K") (pinfunction "C_K") (pintype "passive"))
      (node (ref "R52") (pin "1") (pinfunction "1_1") (pintype "passive"))
    )
    (net (code "60") (name "Net-(L6-PadC)") (class "Default")
      (node (ref "L6") (pin "C") (pinfunction "C_C") (pintype "passive"))
      (node (ref "R5") (pin "2") (pinfunction "2_2") (pintype "passive"))
    )
    (net (code "61") (name "Net-(L7-PadC)") (class "Default")
      (node (ref "L7") (pin "C") (pinfunction "C_C") (pintype "passive"))
      (node (ref "R6") (pin "2") (pinfunction "2_2") (pintype "passive"))
    )
    (net (code "62") (name "Net-(L8-PadC)") (class "Default")
      (node (ref "L8") (pin "C") (pinfunction "C_C") (pintype "passive"))
      (node (ref "R7") (pin "2") (pinfunction "2_2") (pintype "passive"))
    )
    (net (code "63") (name "Net-(L9-PadC)") (class "Default")
      (node (ref "L9") (pin "C") (pinfunction "C_C") (pintype "passive"))
      (node (ref "R8") (pin "2") (pinfunction "2_2") (pintype "passive"))
    )
    (net (code "64") (name "Net-(L10-PadA)") (class "Default")
      (node (ref "L10") (pin "A") (pinfunction "A_A") (pintype "passive"))
      (node (ref "R57") (pin "2") (pinfunction "2_2") (pintype "passive"))
    )
    (net (code "65") (name "Net-(OFF/ON-O)") (class "Default")
      (node (ref "OFF/ON") (pin "1") (pinfunction "O_1") (pintype "passive"))
      (node (ref "R55") (pin "2") (pinfunction "2_2") (pintype "passive"))
    )
    (net (code "66") (name "Net-(OFF/ON-S)") (class "Default")
      (node (ref "OFF/ON") (pin "3") (pinfunction "S_3") (pintype "passive"))
      (node (ref "R56") (pin "2") (pinfunction "2_2") (pintype "passive"))
    )
    (net (code "67") (name "Net-(R17-Pad1)") (class "Default")
      (node (ref "R17") (pin "1") (pinfunction "1_1") (pintype "passive"))
      (node (ref "X1") (pin "1") (pinfunction "1_1") (pintype "passive"))
      (node (ref "X1") (pin "2") (pinfunction "2_2") (pintype "passive"))
      (node (ref "X1") (pin "3") (pinfunction "3_3") (pintype "passive"))
    )
    (net (code "68") (name "Net-(R18-Pad1)") (class "Default")
      (node (ref "R18") (pin "1") (pinfunction "1_1") (pintype "passive"))
      (node (ref "X2") (pin "1") (pinfunction "1_1") (pintype "passive"))
      (node (ref "X2") (pin "2") (pinfunction "2_2") (pintype "passive"))
      (node (ref "X2") (pin "3") (pinfunction "3_3") (pintype "passive"))
    )
    (net (code "69") (name "Net-(R19-Pad1)") (class "Default")
      (node (ref "R19") (pin "1") (pinfunction "1_1") (pintype "passive"))
      (node (ref "X3") (pin "1") (pinfunction "1_1") (pintype "passive"))
      (node (ref "X3") (pin "2") (pinfunction "2_2") (pintype "passive"))
      (node (ref "X3") (pin "3") (pinfunction "3_3") (pintype "passive"))
    )
    (net (code "70") (name "Net-(R20-Pad1)") (class "Default")
      (node (ref "R20") (pin "1") (pinfunction "1_1") (pintype "passive"))
      (node (ref "X4") (pin "1") (pinfunction "1_1") (pintype "passive"))
      (node (ref "X4") (pin "2") (pinfunction "2_2") (pintype "passive"))
      (node (ref "X4") (pin "3") (pinfunction "3_3") (pintype "passive"))
    )
    (net (code "71") (name "Net-(R29-Pad1)") (class "Default")
      (node (ref "R29") (pin "1") (pinfunction "1_1") (pintype "passive"))
      (node (ref "X5") (pin "1") (pinfunction "1_1") (pintype "passive"))
      (node (ref "X5") (pin "2") (pinfunction "2_2") (pintype "passive"))
      (node (ref "X5") (pin "3") (pinfunction "3_3") (pintype "passive"))
    )
    (net (code "72") (name "Net-(R30-Pad1)") (class "Default")
      (node (ref "R30") (pin "1") (pinfunction "1_1") (pintype "passive"))
      (node (ref "X6") (pin "1") (pinfunction "1_1") (pintype "passive"))
      (node (ref "X6") (pin "2") (pinfunction "2_2") (pintype "passive"))
      (node (ref "X6") (pin "3") (pinfunction "3_3") (pintype "passive"))
    )
    (net (code "73") (name "Net-(R31-Pad1)") (class "Default")
      (node (ref "R31") (pin "1") (pinfunction "1_1") (pintype "passive"))
      (node (ref "X7") (pin "1") (pinfunction "1_1") (pintype "passive"))
      (node (ref "X7") (pin "2") (pinfunction "2_2") (pintype "passive"))
      (node (ref "X7") (pin "3") (pinfunction "3_3") (pintype "passive"))
    )
    (net (code "74") (name "Net-(R32-Pad1)") (class "Default")
      (node (ref "R32") (pin "1") (pinfunction "1_1") (pintype "passive"))
      (node (ref "X8") (pin "1") (pinfunction "1_1") (pintype "passive"))
      (node (ref "X8") (pin "2") (pinfunction "2_2") (pintype "passive"))
      (node (ref "X8") (pin "3") (pinfunction "3_3") (pintype "passive"))
    )
    (net (code "75") (name "Net-(R39-Pad1)") (class "Default")
      (node (ref "R39") (pin "1") (pinfunction "1_1") (pintype "passive"))
      (node (ref "X9") (pin "1") (pinfunction "1_1") (pintype "passive"))
      (node (ref "X9") (pin "2") (pinfunction "2_2") (pintype "passive"))
      (node (ref "X9") (pin "3") (pinfunction "3_3") (pintype "passive"))
    )
    (net (code "76") (name "Net-(R40-Pad1)") (class "Default")
      (node (ref "R40") (pin "1") (pinfunction "1_1") (pintype "passive"))
      (node (ref "X10") (pin "1") (pinfunction "1_1") (pintype "passive"))
      (node (ref "X10") (pin "2") (pinfunction "2_2") (pintype "passive"))
      (node (ref "X10") (pin "3") (pinfunction "3_3") (pintype "passive"))
    )
    (net (code "77") (name "Net-(R41-Pad1)") (class "Default")
      (node (ref "R41") (pin "1") (pinfunction "1_1") (pintype "passive"))
      (node (ref "X11") (pin "1") (pinfunction "1_1") (pintype "passive"))
      (node (ref "X11") (pin "2") (pinfunction "2_2") (pintype "passive"))
      (node (ref "X11") (pin "3") (pinfunction "3_3") (pintype "passive"))
    )
    (net (code "78") (name "Net-(R42-Pad1)") (class "Default")
      (node (ref "R42") (pin "1") (pinfunction "1_1") (pintype "passive"))
      (node (ref "X12") (pin "1") (pinfunction "1_1") (pintype "passive"))
      (node (ref "X12") (pin "2") (pinfunction "2_2") (pintype "passive"))
      (node (ref "X12") (pin "3") (pinfunction "3_3") (pintype "passive"))
    )
    (net (code "79") (name "Net-(S1-O)") (class "Default")
      (node (ref "R53") (pin "1") (pinfunction "1_1") (pintype "passive"))
      (node (ref "S1") (pin "1") (pinfunction "O_1") (pintype "passive"))
      (node (ref "S2") (pin "1") (pinfunction "O_1") (pintype "passive"))
      (node (ref "S3") (pin "1") (pinfunction "O_1") (pintype "passive"))
      (node (ref "S4") (pin "1") (pinfunction "O_1") (pintype "passive"))
    )
    (net (code "80") (name "Net-(S1-P)") (class "Default")
      (node (ref "L6") (pin "A") (pinfunction "A_A") (pintype "passive"))
      (node (ref "R1") (pin "2") (pinfunction "2_2") (pintype "passive"))
      (node (ref "S1") (pin "2") (pinfunction "P_2") (pintype "passive"))
    )
    (net (code "81") (name "Net-(S1-S)") (class "Default")
      (node (ref "R54") (pin "2") (pinfunction "2_2") (pintype "passive"))
      (node (ref "S1") (pin "3") (pinfunction "S_3") (pintype "passive"))
      (node (ref "S2") (pin "3") (pinfunction "S_3") (pintype "passive"))
      (node (ref "S3") (pin "3") (pinfunction "S_3") (pintype "passive"))
      (node (ref "S4") (pin "3") (pinfunction "S_3") (pintype "passive"))
    )
    (net (code "82") (name "Net-(S2-P)") (class "Default")
      (node (ref "L7") (pin "A") (pinfunction "A_A") (pintype "passive"))
      (node (ref "R2") (pin "2") (pinfunction "2_2") (pintype "passive"))
      (node (ref "S2") (pin "2") (pinfunction "P_2") (pintype "passive"))
    )
    (net (code "83") (name "Net-(S3-P)") (class "Default")
      (node (ref "L8") (pin "A") (pinfunction "A_A") (pintype "passive"))
      (node (ref "R3") (pin "2") (pinfunction "2_2") (pintype "passive"))
      (node (ref "S3") (pin "2") (pinfunction "P_2") (pintype "passive"))
    )
    (net (code "84") (name "Net-(S4-P)") (class "Default")
      (node (ref "L9") (pin "A") (pinfunction "A_A") (pintype "passive"))
      (node (ref "R4") (pin "2") (pinfunction "2_2") (pintype "passive"))
      (node (ref "S4") (pin "2") (pinfunction "P_2") (pintype "passive"))
    )
    (net (code "85") (name "VCC") (class "Default")
      (node (ref "C1") (pin "1") (pinfunction "1_1") (pintype "passive"))
      (node (ref "C10") (pin "1") (pinfunction "1_1") (pintype "passive"))
      (node (ref "C11") (pin "1") (pinfunction "1_1") (pintype "passive"))
      (node (ref "C12") (pin "1") (pinfunction "1_1") (pintype "passive"))
      (node (ref "C2") (pin "1") (pinfunction "1_1") (pintype "passive"))
      (node (ref "C3") (pin "1") (pinfunction "1_1") (pintype "passive"))
      (node (ref "C4") (pin "1") (pinfunction "1_1") (pintype "passive"))
      (node (ref "C5") (pin "1") (pinfunction "1_1") (pintype "passive"))
      (node (ref "C6") (pin "1") (pinfunction "1_1") (pintype "passive"))
      (node (ref "C7") (pin "1") (pinfunction "1_1") (pintype "passive"))
      (node (ref "C8") (pin "1") (pinfunction "1_1") (pintype "passive"))
      (node (ref "C9") (pin "1") (pinfunction "1_1") (pintype "passive"))
      (node (ref "D1") (pin "C") (pinfunction "C_C") (pintype "passive"))
      (node (ref "L1") (pin "A") (pinfunction "A_A") (pintype "passive"))
      (node (ref "L2") (pin "A") (pinfunction "A_A") (pintype "passive"))
      (node (ref "L3") (pin "A") (pinfunction "A_A") (pintype "passive"))
      (node (ref "L4") (pin "A") (pinfunction "A_A") (pintype "passive"))
      (node (ref "L5") (pin "A") (pinfunction "A_A") (pintype "passive"))
      (node (ref "R54") (pin "1") (pinfunction "1_1") (pintype "passive"))
      (node (ref "R57") (pin "1") (pinfunction "1_1") (pintype "passive"))
    )
  )
)
